# Executive_230V_A.net
KiCad netlist of a schematic drawn in EAGLE
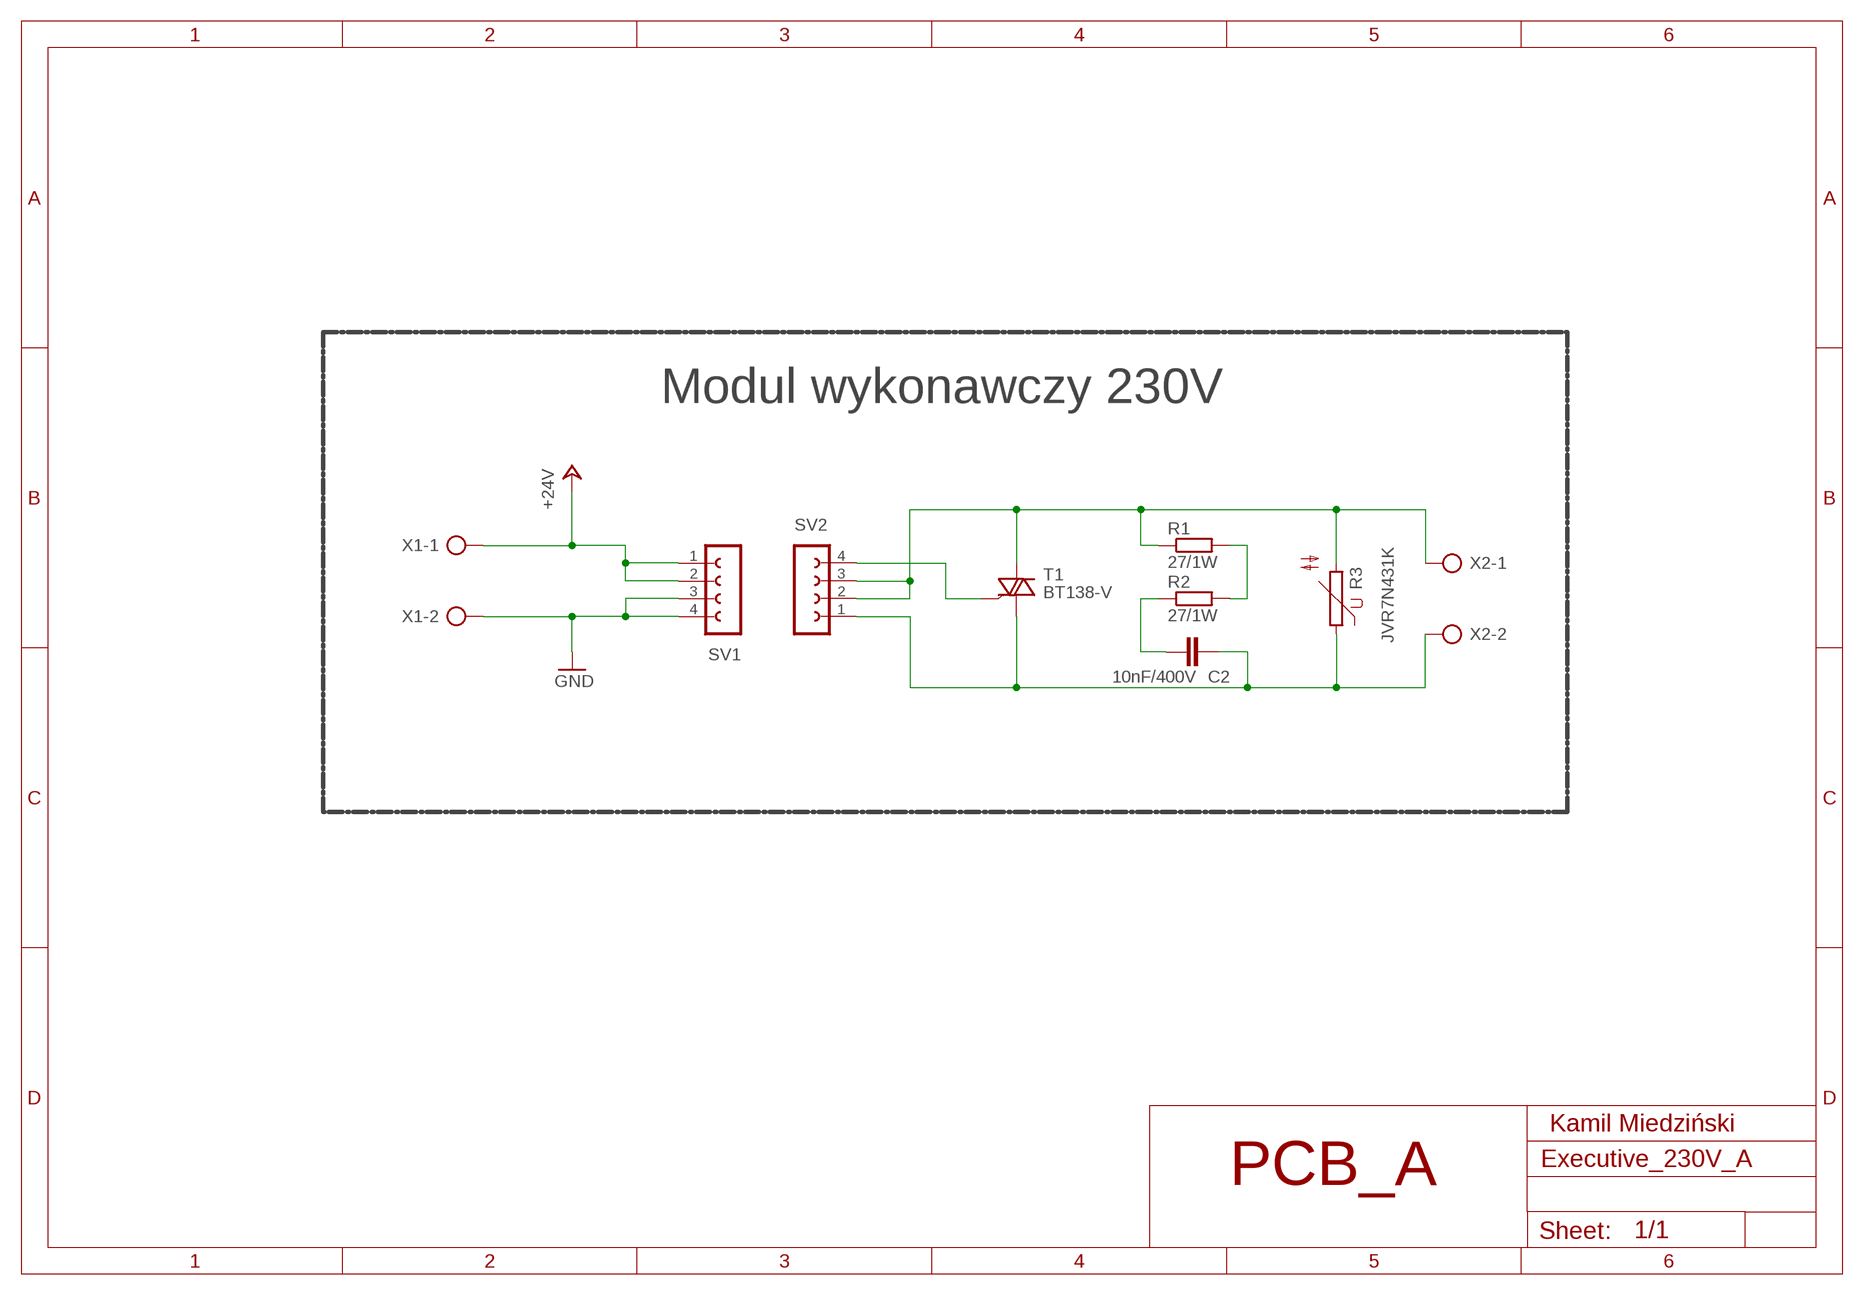
[diagram p0: schematic, sheet 1]

(export (version "E")
  (design (tool "Eeschema 10.0.6"))
  (components
    (comp (ref "C2")
      (value "10nF/400V")
      (footprint "eagle-import:C102-054X133")
      (libsource (lib "eagle-import") (part "C-EU102-054X133"))
    )
    (comp (ref "R1")
      (value "27/1W")
      (footprint "eagle-import:0411_15")
      (libsource (lib "eagle-import") (part "R-EU_0411/15"))
    )
    (comp (ref "R2")
      (value "27/1W")
      (footprint "eagle-import:0411_15")
      (libsource (lib "eagle-import") (part "R-EU_0411/15"))
    )
    (comp (ref "R3")
      (value "JVR7N431K")
      (footprint "eagle-import:S05K11")
      (libsource (lib "eagle-import") (part "S05K11"))
    )
    (comp (ref "SV1")
      (value "FE04-1")
      (footprint "eagle-import:FE04-1")
      (libsource (lib "eagle-import") (part "FE04-1"))
    )
    (comp (ref "SV2")
      (value "FE04-1")
      (footprint "eagle-import:FE04-1")
      (libsource (lib "eagle-import") (part "FE04-1"))
    )
    (comp (ref "T1")
      (value "BT138-V")
      (footprint "eagle-import:TO220BV")
      (libsource (lib "eagle-import") (part "BT138-V"))
    )
    (comp (ref "X1")
      (value "GMKDSP_3/2")
      (footprint "eagle-import:GMKDSP_3_2")
      (libsource (lib "eagle-import") (part "GMKDSP_3/2"))
    )
    (comp (ref "X2")
      (value "GMKDSP_3/2")
      (footprint "eagle-import:GMKDSP_3_2")
      (libsource (lib "eagle-import") (part "GMKDSP_3/2"))
    )
  )
  (nets
    (net (code "1") (name "+24V") (class "Default")
      (node (ref "SV1") (pin "1") (pinfunction "2_1") (pintype "passive"))
      (node (ref "SV1") (pin "2") (pinfunction "3_2") (pintype "passive"))
      (node (ref "X1") (pin "1") (pinfunction "KL_1") (pintype "passive"))
    )
    (net (code "2") (name "GND") (class "Default")
      (node (ref "SV1") (pin "3") (pinfunction "4_3") (pintype "passive"))
      (node (ref "SV1") (pin "4") (pinfunction "5_4") (pintype "passive"))
      (node (ref "X1") (pin "2") (pinfunction "KL_2") (pintype "passive"))
    )
    (net (code "3") (name "Net-(C2-Pad1)") (class "Default")
      (node (ref "C2") (pin "1") (pinfunction "1_1") (pintype "passive"))
      (node (ref "R2") (pin "1") (pinfunction "1_1") (pintype "passive"))
    )
    (net (code "4") (name "Net-(R1-Pad2)") (class "Default")
      (node (ref "R1") (pin "2") (pinfunction "2_2") (pintype "passive"))
      (node (ref "R2") (pin "2") (pinfunction "2_2") (pintype "passive"))
    )
    (net (code "5") (name "Net-(SV2-2)") (class "Default")
      (node (ref "C2") (pin "2") (pinfunction "2_2") (pintype "passive"))
      (node (ref "R3") (pin "1") (pinfunction "1_1") (pintype "passive"))
      (node (ref "SV2") (pin "1") (pinfunction "2_1") (pintype "passive"))
      (node (ref "T1") (pin "T1") (pinfunction "A1_T1") (pintype "passive"))
      (node (ref "X2") (pin "2") (pinfunction "KL_2") (pintype "passive"))
    )
    (net (code "6") (name "Net-(SV2-3)") (class "Default")
      (node (ref "R1") (pin "1") (pinfunction "1_1") (pintype "passive"))
      (node (ref "R3") (pin "2") (pinfunction "2_2") (pintype "passive"))
      (node (ref "SV2") (pin "2") (pinfunction "3_2") (pintype "passive"))
      (node (ref "SV2") (pin "3") (pinfunction "4_3") (pintype "passive"))
      (node (ref "T1") (pin "T2") (pinfunction "A2_T2") (pintype "passive"))
      (node (ref "X2") (pin "1") (pinfunction "KL_1") (pintype "passive"))
    )
    (net (code "7") (name "Net-(SV2-5)") (class "Default")
      (node (ref "SV2") (pin "4") (pinfunction "5_4") (pintype "passive"))
      (node (ref "T1") (pin "G") (pinfunction "G_G") (pintype "passive"))
    )
  )
)
